# DistanceMeasure.net
KiCad netlist of a schematic drawn in Altium Designer
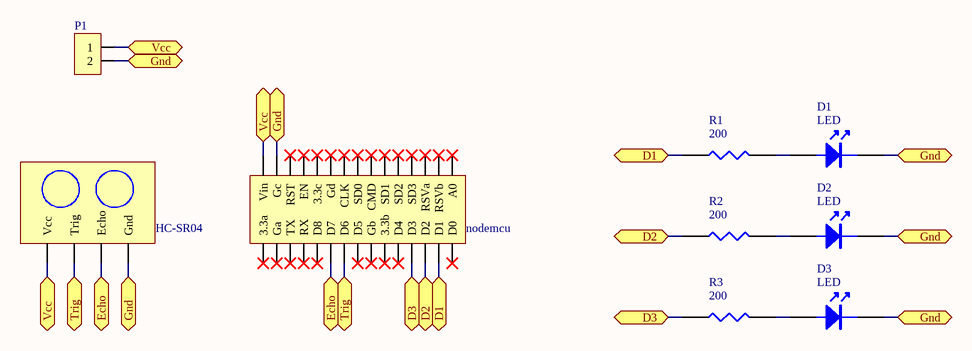
[diagram p0: DistanceMeasure.SchDoc]

(export (version "E")
  (design (tool "Eeschema 10.0.6"))
  (components
    (comp (ref "D1") (value "LED") (footprint "DIODE4MMUP") (libsource (lib "DIODE_SCH") (part "LED")))
    (comp (ref "D2") (value "LED") (footprint "DIODE4MMUP") (libsource (lib "DIODE_SCH") (part "LED")))
    (comp (ref "D3") (value "LED") (footprint "DIODE4MMUP") (libsource (lib "DIODE_SCH") (part "LED")))
    (comp (ref "HC-SR04")
      (value "HC-SR04")
      (footprint "HC-SR04")
      (libsource (lib "HC-SR04") (part "HC-SR04"))
    )
    (comp (ref "nodemcu")
      (value "nodemcu")
      (footprint "nodemcu")
      (libsource (lib "nodemcu") (part "nodemcu"))
    )
    (comp (ref "P1")
      (value "LittleGreenMos")
      (footprint "LittleGreenMos")
      (libsource (lib "LittleGreenMos") (part "LittleGreenMos"))
    )
    (comp (ref "R1")
      (value "200")
      (footprint "RES0.4")
      (libsource (lib "Miscellaneous Devices") (part "RES1"))
    )
    (comp (ref "R2")
      (value "200")
      (footprint "RES0.4")
      (libsource (lib "Miscellaneous Devices") (part "RES1"))
    )
    (comp (ref "R3")
      (value "200")
      (footprint "RES0.4")
      (libsource (lib "Miscellaneous Devices") (part "RES1"))
    )
  )
  (nets
    (net (code "1") (name "/D1") (class "Default")
      (node (ref "R1") (pin "1") (pinfunction "1_1") (pintype "passive"))
      (node (ref "nodemcu") (pin "D1") (pinfunction "D1_D1") (pintype "passive"))
    )
    (net (code "2") (name "/D2") (class "Default")
      (node (ref "R2") (pin "1") (pinfunction "1_1") (pintype "passive"))
      (node (ref "nodemcu") (pin "D2") (pinfunction "D2_D2") (pintype "passive"))
    )
    (net (code "3") (name "/D3") (class "Default")
      (node (ref "R3") (pin "1") (pinfunction "1_1") (pintype "passive"))
      (node (ref "nodemcu") (pin "D3") (pinfunction "D3_D3") (pintype "passive"))
    )
    (net (code "4") (name "/Echo") (class "Default")
      (node (ref "HC-SR04") (pin "Echo") (pinfunction "Echo_Echo") (pintype "passive"))
      (node (ref "nodemcu") (pin "D7") (pinfunction "D7_D7") (pintype "passive"))
    )
    (net (code "5") (name "/Gnd") (class "Default")
      (node (ref "D1") (pin "K") (pinfunction "2_K") (pintype "passive"))
      (node (ref "D2") (pin "K") (pinfunction "2_K") (pintype "passive"))
      (node (ref "D3") (pin "K") (pinfunction "2_K") (pintype "passive"))
      (node (ref "HC-SR04") (pin "Gnd") (pinfunction "Gnd_Gnd") (pintype "passive"))
      (node (ref "P1") (pin "2") (pinfunction "2_2") (pintype "passive"))
      (node (ref "nodemcu") (pin "Gc") (pinfunction "Gc_Gc") (pintype "passive"))
    )
    (net (code "6") (name "/Trig") (class "Default")
      (node (ref "HC-SR04") (pin "Trig") (pinfunction "Trig_Trig") (pintype "passive"))
      (node (ref "nodemcu") (pin "D6") (pinfunction "D6_D6") (pintype "passive"))
    )
    (net (code "7") (name "/Vcc") (class "Default")
      (node (ref "HC-SR04") (pin "Vcc") (pinfunction "Vcc_Vcc") (pintype "passive"))
      (node (ref "P1") (pin "1") (pinfunction "1_1") (pintype "passive"))
      (node (ref "nodemcu") (pin "Vin") (pinfunction "Vin_Vin") (pintype "passive"))
    )
    (net (code "8") (name "Net-(D1-1)") (class "Default")
      (node (ref "D1") (pin "A") (pinfunction "1_A") (pintype "passive"))
      (node (ref "R1") (pin "2") (pinfunction "2_2") (pintype "passive"))
    )
    (net (code "9") (name "Net-(D2-1)") (class "Default")
      (node (ref "D2") (pin "A") (pinfunction "1_A") (pintype "passive"))
      (node (ref "R2") (pin "2") (pinfunction "2_2") (pintype "passive"))
    )
    (net (code "10") (name "Net-(D3-1)") (class "Default")
      (node (ref "D3") (pin "A") (pinfunction "1_A") (pintype "passive"))
      (node (ref "R3") (pin "2") (pinfunction "2_2") (pintype "passive"))
    )
    (net (code "11") (name "unconnected-(nodemcu-Pad3.3a)") (class "Default")
      (node (ref "nodemcu") (pin "3.3a") (pinfunction "3.3a_3.3a") (pintype "passive+no_connect"))
    )
    (net (code "12") (name "unconnected-(nodemcu-Pad3.3b)") (class "Default")
      (node (ref "nodemcu") (pin "3.3b") (pinfunction "3.3b_3.3b") (pintype "passive+no_connect"))
    )
    (net (code "13") (name "unconnected-(nodemcu-Pad3.3c)") (class "Default")
      (node (ref "nodemcu") (pin "3.3c") (pinfunction "3.3c_3.3c") (pintype "passive+no_connect"))
    )
    (net (code "14") (name "unconnected-(nodemcu-PadA0)") (class "Default")
      (node (ref "nodemcu") (pin "A0") (pinfunction "A0_A0") (pintype "passive+no_connect"))
    )
    (net (code "15") (name "unconnected-(nodemcu-PadCLK)") (class "Default")
      (node (ref "nodemcu") (pin "CLK") (pinfunction "CLK_CLK") (pintype "passive+no_connect"))
    )
    (net (code "16") (name "unconnected-(nodemcu-PadCMD)") (class "Default")
      (node (ref "nodemcu") (pin "CMD") (pinfunction "CMD_CMD") (pintype "passive+no_connect"))
    )
    (net (code "17") (name "unconnected-(nodemcu-PadD0)") (class "Default")
      (node (ref "nodemcu") (pin "D0") (pinfunction "D0_D0") (pintype "passive+no_connect"))
    )
    (net (code "18") (name "unconnected-(nodemcu-PadD4)") (class "Default")
      (node (ref "nodemcu") (pin "D4") (pinfunction "D4_D4") (pintype "passive+no_connect"))
    )
    (net (code "19") (name "unconnected-(nodemcu-PadD5)") (class "Default")
      (node (ref "nodemcu") (pin "D5") (pinfunction "D5_D5") (pintype "passive+no_connect"))
    )
    (net (code "20") (name "unconnected-(nodemcu-PadD8)") (class "Default")
      (node (ref "nodemcu") (pin "D8") (pinfunction "D8_D8") (pintype "passive+no_connect"))
    )
    (net (code "21") (name "unconnected-(nodemcu-PadEN)") (class "Default")
      (node (ref "nodemcu") (pin "EN") (pinfunction "EN_EN") (pintype "passive+no_connect"))
    )
    (net (code "22") (name "unconnected-(nodemcu-PadGa)") (class "Default")
      (node (ref "nodemcu") (pin "Ga") (pinfunction "Ga_Ga") (pintype "passive+no_connect"))
    )
    (net (code "23") (name "unconnected-(nodemcu-PadGb)") (class "Default")
      (node (ref "nodemcu") (pin "Gb") (pinfunction "Gb_Gb") (pintype "passive+no_connect"))
    )
    (net (code "24") (name "unconnected-(nodemcu-PadGd)") (class "Default")
      (node (ref "nodemcu") (pin "Gd") (pinfunction "Gd_Gd") (pintype "passive+no_connect"))
    )
    (net (code "25") (name "unconnected-(nodemcu-PadRST)") (class "Default")
      (node (ref "nodemcu") (pin "RST") (pinfunction "RST_RST") (pintype "passive+no_connect"))
    )
    (net (code "26") (name "unconnected-(nodemcu-PadRSVb)") (class "Default")
      (node (ref "nodemcu") (pin "RSVb") (pinfunction "RSVb_RSVb") (pintype "passive+no_connect"))
    )
    (net (code "27") (name "unconnected-(nodemcu-PadRX)") (class "Default")
      (node (ref "nodemcu") (pin "RX") (pinfunction "RX_RX") (pintype "passive+no_connect"))
    )
    (net (code "28") (name "unconnected-(nodemcu-PadSD0)") (class "Default")
      (node (ref "nodemcu") (pin "SD0") (pinfunction "SD0_SD0") (pintype "passive+no_connect"))
    )
    (net (code "29") (name "unconnected-(nodemcu-PadSD1)") (class "Default")
      (node (ref "nodemcu") (pin "SD1") (pinfunction "SD1_SD1") (pintype "passive+no_connect"))
    )
    (net (code "30") (name "unconnected-(nodemcu-PadSD2)") (class "Default")
      (node (ref "nodemcu") (pin "SD2") (pinfunction "SD2_SD2") (pintype "passive+no_connect"))
    )
    (net (code "31") (name "unconnected-(nodemcu-PadSD3)") (class "Default")
      (node (ref "nodemcu") (pin "SD3") (pinfunction "SD3_SD3") (pintype "passive+no_connect"))
    )
    (net (code "32") (name "unconnected-(nodemcu-PadTX)") (class "Default")
      (node (ref "nodemcu") (pin "TX") (pinfunction "TX_TX") (pintype "passive+no_connect"))
    )
    (net (code "33") (name "unconnected-(nodemcu-RSVa-PadRSVb)") (class "Default")
      (node (ref "nodemcu") (pin "RSVb") (pinfunction "RSVa_RSVb") (pintype "passive+no_connect"))
    )
  )
)
